# WiFiRadio_r1b4.net
KiCad netlist of a schematic drawn in EAGLE
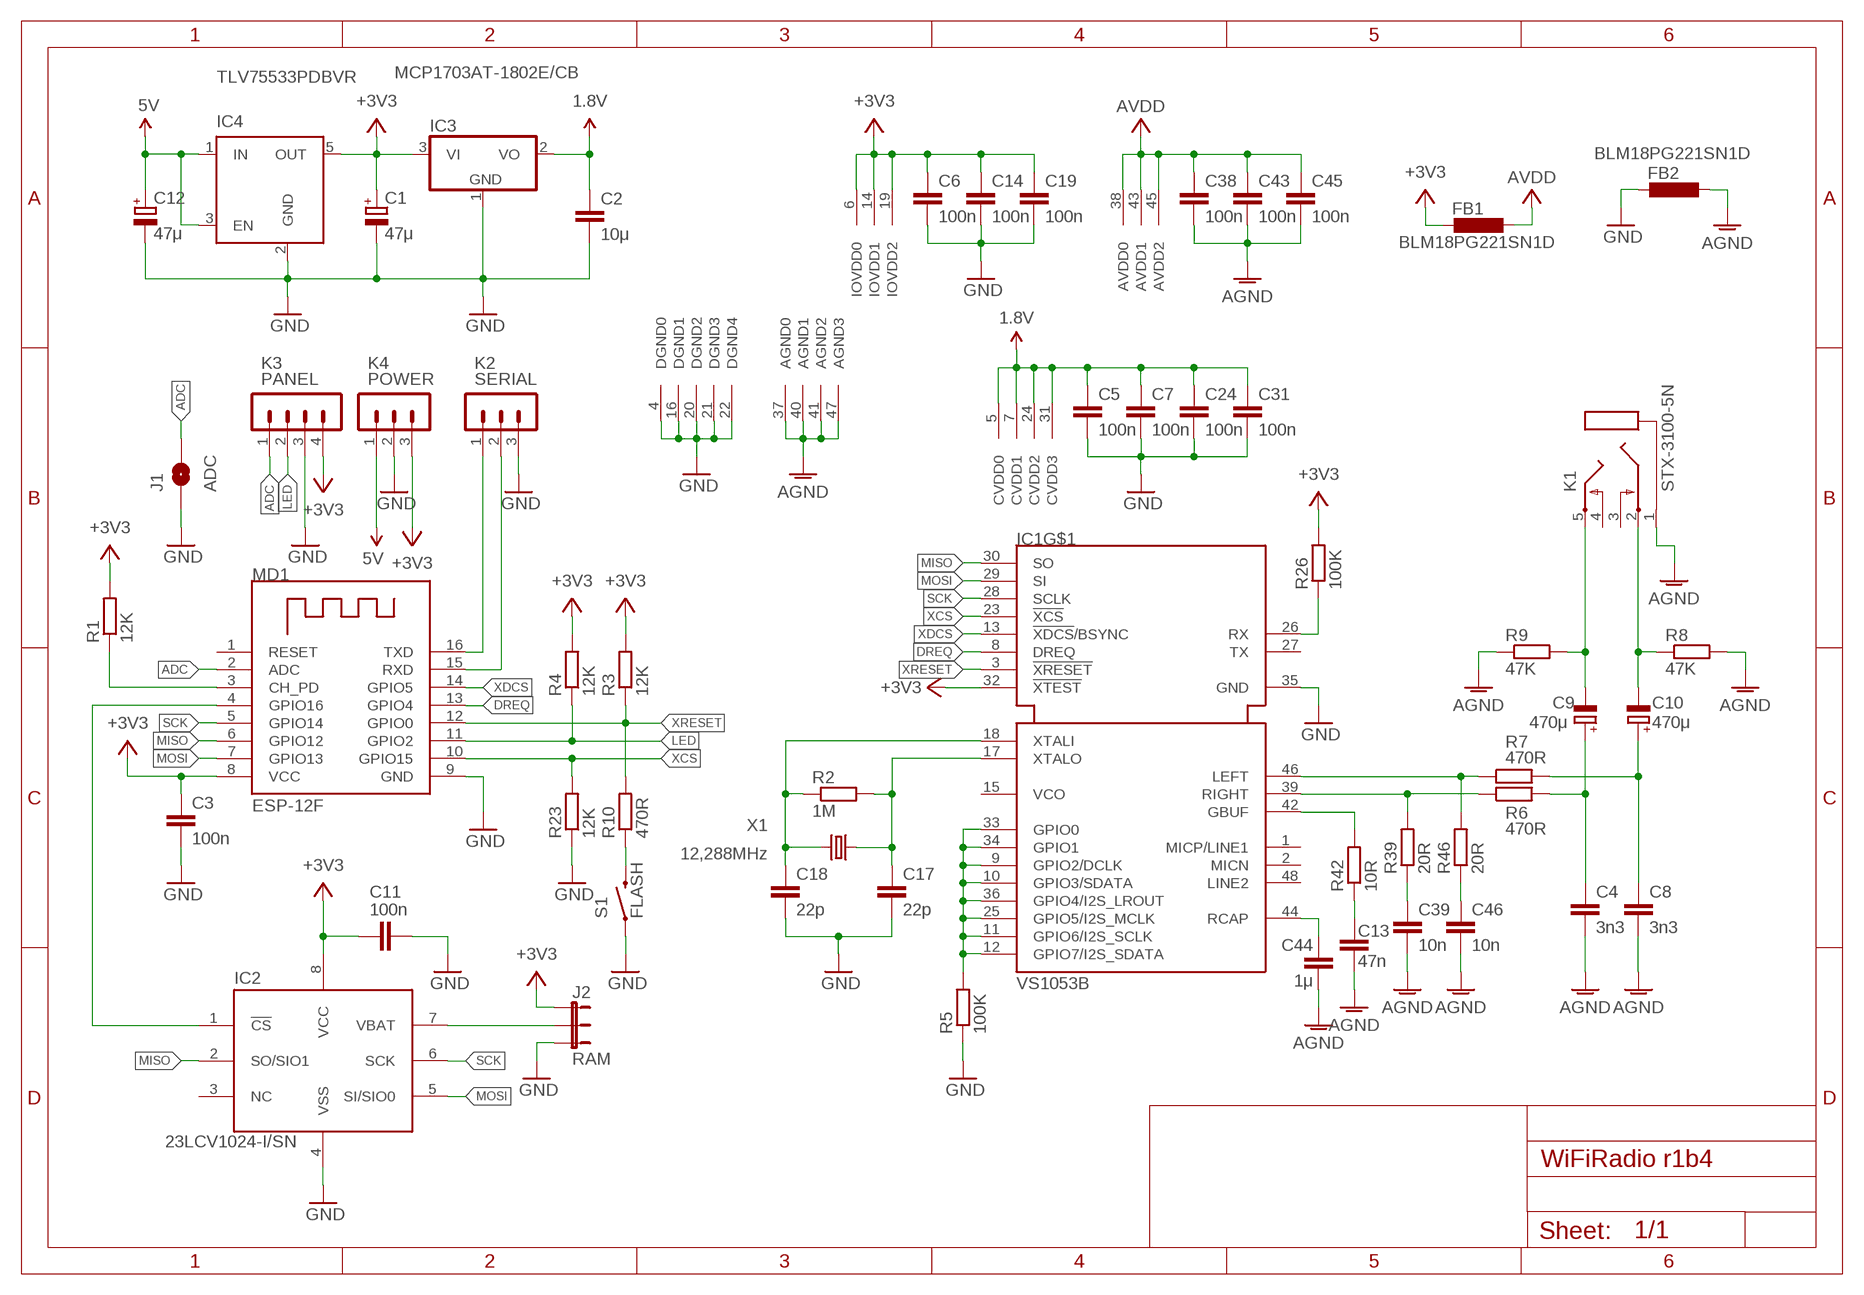
[diagram p0: schematic, sheet 1]

(export (version "E")
  (design (tool "Eeschema 10.0.6"))
  (components
    (comp (ref "C1")
      (value "47μ")
      (footprint "eagle-import:SMC_B")
      (libsource (lib "eagle-import") (part "rcl_334_CPOL-EUSMCB"))
    )
    (comp (ref "C2")
      (value "10μ")
      (footprint "eagle-import:C0805")
      (libsource (lib "eagle-import") (part "C-EUC0805"))
    )
    (comp (ref "C3")
      (value "100n")
      (footprint "eagle-import:C0603")
      (libsource (lib "eagle-import") (part "C-EUC0603"))
    )
    (comp (ref "C4")
      (value "3n3")
      (footprint "eagle-import:C0805")
      (libsource (lib "eagle-import") (part "C-EUC0805"))
    )
    (comp (ref "C5")
      (value "100n")
      (footprint "eagle-import:C0603")
      (libsource (lib "eagle-import") (part "C-EUC0603"))
    )
    (comp (ref "C6")
      (value "100n")
      (footprint "eagle-import:C0603")
      (libsource (lib "eagle-import") (part "C-EUC0603"))
    )
    (comp (ref "C7")
      (value "100n")
      (footprint "eagle-import:C0603")
      (libsource (lib "eagle-import") (part "C-EUC0603"))
    )
    (comp (ref "C8")
      (value "3n3")
      (footprint "eagle-import:C0805")
      (libsource (lib "eagle-import") (part "C-EUC0805"))
    )
    (comp (ref "C9")
      (value "470μ")
      (footprint "eagle-import:E3,5-8")
      (libsource (lib "eagle-import") (part "CPOL-EUE3.5-8"))
    )
    (comp (ref "C10")
      (value "470μ")
      (footprint "eagle-import:E3,5-8")
      (libsource (lib "eagle-import") (part "CPOL-EUE3.5-8"))
    )
    (comp (ref "C11")
      (value "100n")
      (footprint "eagle-import:C0603")
      (libsource (lib "eagle-import") (part "C-EUC0603"))
    )
    (comp (ref "C12")
      (value "47μ")
      (footprint "eagle-import:SMC_B")
      (libsource (lib "eagle-import") (part "rcl_334_CPOL-EUSMCB"))
    )
    (comp (ref "C13")
      (value "47n")
      (footprint "eagle-import:C0805")
      (libsource (lib "eagle-import") (part "C-EUC0805"))
    )
    (comp (ref "C14")
      (value "100n")
      (footprint "eagle-import:C0603")
      (libsource (lib "eagle-import") (part "C-EUC0603"))
    )
    (comp (ref "C17")
      (value "22p")
      (footprint "eagle-import:C0805")
      (libsource (lib "eagle-import") (part "C-EUC0805"))
    )
    (comp (ref "C18")
      (value "22p")
      (footprint "eagle-import:C0805")
      (libsource (lib "eagle-import") (part "C-EUC0805"))
    )
    (comp (ref "C19")
      (value "100n")
      (footprint "eagle-import:C0603")
      (libsource (lib "eagle-import") (part "C-EUC0603"))
    )
    (comp (ref "C24")
      (value "100n")
      (footprint "eagle-import:C0603")
      (libsource (lib "eagle-import") (part "C-EUC0603"))
    )
    (comp (ref "C31")
      (value "100n")
      (footprint "eagle-import:C0603")
      (libsource (lib "eagle-import") (part "C-EUC0603"))
    )
    (comp (ref "C38")
      (value "100n")
      (footprint "eagle-import:C0603")
      (libsource (lib "eagle-import") (part "C-EUC0603"))
    )
    (comp (ref "C39")
      (value "10n")
      (footprint "eagle-import:C0805")
      (libsource (lib "eagle-import") (part "C-EUC0805"))
    )
    (comp (ref "C43")
      (value "100n")
      (footprint "eagle-import:C0603")
      (libsource (lib "eagle-import") (part "C-EUC0603"))
    )
    (comp (ref "C44")
      (value "1μ")
      (footprint "eagle-import:C0805")
      (libsource (lib "eagle-import") (part "C-EUC0805"))
    )
    (comp (ref "C45")
      (value "100n")
      (footprint "eagle-import:C0603")
      (libsource (lib "eagle-import") (part "C-EUC0603"))
    )
    (comp (ref "C46")
      (value "10n")
      (footprint "eagle-import:C0805")
      (libsource (lib "eagle-import") (part "C-EUC0805"))
    )
    (comp (ref "FB1")
      (value "BLM18PG221SN1D")
      (footprint "eagle-import:L2012C")
      (libsource (lib "eagle-import") (part "L-EUL2012C"))
    )
    (comp (ref "FB2")
      (value "BLM18PG221SN1D")
      (footprint "eagle-import:L2012C")
      (libsource (lib "eagle-import") (part "L-EUL2012C"))
    )
    (comp (ref "IC1")
      (value "VS1053B")
      (footprint "eagle-import:LQFP48")
      (libsource (lib "eagle-import") (part "VS1053B"))
    )
    (comp (ref "IC2")
      (value "23LCV1024-I/SN")
      (footprint "eagle-import:SO-08")
      (libsource (lib "eagle-import") (part "23LCV1024-I/SN"))
    )
    (comp (ref "IC3")
      (value "MCP1703AT-1802E/CB")
      (footprint "eagle-import:SOT23")
      (libsource (lib "eagle-import") (part "MCP1703CB"))
    )
    (comp (ref "IC4")
      (value "TLV75533PDBVR")
      (footprint "eagle-import:SOT23-5")
      (libsource (lib "eagle-import") (part "TLV7555P-DBV"))
    )
    (comp (ref "J1")
      (value "ADC")
      (footprint "eagle-import:SJ_2S")
      (libsource (lib "eagle-import") (part "SOLDERJUMPER-OLDNC"))
    )
    (comp (ref "J2")
      (value "RAM")
      (footprint "eagle-import:SJ_3")
      (libsource (lib "eagle-import") (part "JUMPER-3SMD"))
    )
    (comp (ref "K1")
      (value "STX-3100-5N")
      (footprint "eagle-import:STX3100")
      (libsource (lib "eagle-import") (part "STEREOJACK"))
    )
    (comp (ref "K2")
      (value "SERIAL")
      (footprint "eagle-import:MA03-1")
      (libsource (lib "eagle-import") (part "MA03-1"))
    )
    (comp (ref "K3")
      (value "PANEL")
      (footprint "eagle-import:MA04-1")
      (libsource (lib "eagle-import") (part "MA04-1"))
    )
    (comp (ref "K4")
      (value "POWER")
      (footprint "eagle-import:MA03-1")
      (libsource (lib "eagle-import") (part "MA03-1"))
    )
    (comp (ref "MD1")
      (value "ESP-12F")
      (footprint "eagle-import:ESP-12F")
      (libsource (lib "eagle-import") (part "ESP-12F"))
    )
    (comp (ref "R1")
      (value "12K")
      (footprint "eagle-import:R0805")
      (libsource (lib "eagle-import") (part "R-EU_R0805"))
    )
    (comp (ref "R2")
      (value "1M")
      (footprint "eagle-import:R0805")
      (libsource (lib "eagle-import") (part "R-EU_R0805"))
    )
    (comp (ref "R3")
      (value "12K")
      (footprint "eagle-import:R0805")
      (libsource (lib "eagle-import") (part "R-EU_R0805"))
    )
    (comp (ref "R4")
      (value "12K")
      (footprint "eagle-import:R0805")
      (libsource (lib "eagle-import") (part "R-EU_R0805"))
    )
    (comp (ref "R5")
      (value "100K")
      (footprint "eagle-import:R0805")
      (libsource (lib "eagle-import") (part "R-EU_R0805"))
    )
    (comp (ref "R6")
      (value "470R")
      (footprint "eagle-import:R0805")
      (libsource (lib "eagle-import") (part "R-EU_R0805"))
    )
    (comp (ref "R7")
      (value "470R")
      (footprint "eagle-import:R0805")
      (libsource (lib "eagle-import") (part "R-EU_R0805"))
    )
    (comp (ref "R8")
      (value "47K")
      (footprint "eagle-import:R0805")
      (libsource (lib "eagle-import") (part "R-EU_R0805"))
    )
    (comp (ref "R9")
      (value "47K")
      (footprint "eagle-import:R0805")
      (libsource (lib "eagle-import") (part "R-EU_R0805"))
    )
    (comp (ref "R10")
      (value "470R")
      (footprint "eagle-import:R0805")
      (libsource (lib "eagle-import") (part "R-EU_R0805"))
    )
    (comp (ref "R23")
      (value "12K")
      (footprint "eagle-import:R0805")
      (libsource (lib "eagle-import") (part "R-EU_R0805"))
    )
    (comp (ref "R26")
      (value "100K")
      (footprint "eagle-import:R0805")
      (libsource (lib "eagle-import") (part "R-EU_R0805"))
    )
    (comp (ref "R39")
      (value "20R")
      (footprint "eagle-import:R0805")
      (libsource (lib "eagle-import") (part "R-EU_R0805"))
    )
    (comp (ref "R42")
      (value "10R")
      (footprint "eagle-import:R0805")
      (libsource (lib "eagle-import") (part "R-EU_R0805"))
    )
    (comp (ref "R46")
      (value "20R")
      (footprint "eagle-import:R0805")
      (libsource (lib "eagle-import") (part "R-EU_R0805"))
    )
    (comp (ref "S1")
      (value "FLASH")
      (footprint "eagle-import:TACTILE-SWITCH-SMD")
      (libsource (lib "eagle-import") (part "SWITCH-MOMENTARY-2SMD"))
    )
    (comp (ref "X1")
      (value "12,288MHz")
      (footprint "eagle-import:HC49_S")
      (libsource (lib "eagle-import") (part "CRYSTALHC49S"))
    )
  )
  (nets
    (net (code "1") (name "+3V3") (class "Default")
      (node (ref "C1") (pin "+") (pinfunction "+_+") (pintype "passive"))
      (node (ref "C11") (pin "1") (pinfunction "1_1") (pintype "passive"))
      (node (ref "C14") (pin "1") (pinfunction "1_1") (pintype "passive"))
      (node (ref "C19") (pin "1") (pinfunction "1_1") (pintype "passive"))
      (node (ref "C3") (pin "1") (pinfunction "1_1") (pintype "passive"))
      (node (ref "C6") (pin "1") (pinfunction "1_1") (pintype "passive"))
      (node (ref "FB1") (pin "2") (pinfunction "2_2") (pintype "passive"))
      (node (ref "IC1") (pin "14") (pinfunction "IOVDD1_14") (pintype "power_in"))
      (node (ref "IC1") (pin "19") (pinfunction "IOVDD2_19") (pintype "power_in"))
      (node (ref "IC1") (pin "32") (pinfunction "~{XTEST}_32") (pintype "input"))
      (node (ref "IC1") (pin "6") (pinfunction "IOVDD0_6") (pintype "power_in"))
      (node (ref "IC2") (pin "8") (pinfunction "VCC_8") (pintype "power_in"))
      (node (ref "IC3") (pin "3") (pinfunction "VI_3") (pintype "input"))
      (node (ref "IC4") (pin "5") (pinfunction "OUT_5") (pintype "output"))
      (node (ref "J2") (pin "1") (pinfunction "1_1") (pintype "passive"))
      (node (ref "K3") (pin "4") (pinfunction "4_4") (pintype "passive"))
      (node (ref "K4") (pin "3") (pinfunction "3_3") (pintype "passive"))
      (node (ref "MD1") (pin "8") (pinfunction "VCC_8") (pintype "power_in"))
      (node (ref "R1") (pin "2") (pinfunction "2_2") (pintype "passive"))
      (node (ref "R26") (pin "2") (pinfunction "2_2") (pintype "passive"))
      (node (ref "R3") (pin "2") (pinfunction "2_2") (pintype "passive"))
      (node (ref "R4") (pin "2") (pinfunction "2_2") (pintype "passive"))
    )
    (net (code "2") (name "1.8V") (class "Default")
      (node (ref "C2") (pin "1") (pinfunction "1_1") (pintype "passive"))
      (node (ref "C24") (pin "1") (pinfunction "1_1") (pintype "passive"))
      (node (ref "C31") (pin "1") (pinfunction "1_1") (pintype "passive"))
      (node (ref "C5") (pin "1") (pinfunction "1_1") (pintype "passive"))
      (node (ref "C7") (pin "1") (pinfunction "1_1") (pintype "passive"))
      (node (ref "IC1") (pin "24") (pinfunction "CVDD2_24") (pintype "power_in"))
      (node (ref "IC1") (pin "31") (pinfunction "CVDD3_31") (pintype "power_in"))
      (node (ref "IC1") (pin "5") (pinfunction "CVDD0_5") (pintype "power_in"))
      (node (ref "IC1") (pin "7") (pinfunction "CVDD1_7") (pintype "power_in"))
      (node (ref "IC3") (pin "2") (pinfunction "VO_2") (pintype "passive"))
    )
    (net (code "3") (name "5V") (class "Default")
      (node (ref "C12") (pin "+") (pinfunction "+_+") (pintype "passive"))
      (node (ref "IC4") (pin "1") (pinfunction "IN_1") (pintype "input"))
      (node (ref "IC4") (pin "3") (pinfunction "EN_3") (pintype "input"))
      (node (ref "K4") (pin "1") (pinfunction "1_1") (pintype "passive"))
    )
    (net (code "4") (name "ADC") (class "Default")
      (node (ref "J1") (pin "2") (pinfunction "2_2") (pintype "passive"))
      (node (ref "K3") (pin "1") (pinfunction "1_1") (pintype "passive"))
      (node (ref "MD1") (pin "2") (pinfunction "ADC_2") (pintype "passive"))
    )
    (net (code "5") (name "AGND") (class "Default")
      (node (ref "C13") (pin "2") (pinfunction "2_2") (pintype "passive"))
      (node (ref "C38") (pin "2") (pinfunction "2_2") (pintype "passive"))
      (node (ref "C39") (pin "2") (pinfunction "2_2") (pintype "passive"))
      (node (ref "C4") (pin "2") (pinfunction "2_2") (pintype "passive"))
      (node (ref "C43") (pin "2") (pinfunction "2_2") (pintype "passive"))
      (node (ref "C44") (pin "2") (pinfunction "2_2") (pintype "passive"))
      (node (ref "C45") (pin "2") (pinfunction "2_2") (pintype "passive"))
      (node (ref "C46") (pin "2") (pinfunction "2_2") (pintype "passive"))
      (node (ref "C8") (pin "2") (pinfunction "2_2") (pintype "passive"))
      (node (ref "FB2") (pin "1") (pinfunction "1_1") (pintype "passive"))
      (node (ref "IC1") (pin "37") (pinfunction "AGND0_37") (pintype "power_in"))
      (node (ref "IC1") (pin "40") (pinfunction "AGND1_40") (pintype "power_in"))
      (node (ref "IC1") (pin "41") (pinfunction "AGND2_41") (pintype "power_in"))
      (node (ref "IC1") (pin "47") (pinfunction "AGND3_47") (pintype "power_in"))
      (node (ref "K1") (pin "1") (pinfunction "1_1") (pintype "passive"))
      (node (ref "R8") (pin "2") (pinfunction "2_2") (pintype "passive"))
      (node (ref "R9") (pin "1") (pinfunction "1_1") (pintype "passive"))
    )
    (net (code "6") (name "AVDD") (class "Default")
      (node (ref "C38") (pin "1") (pinfunction "1_1") (pintype "passive"))
      (node (ref "C43") (pin "1") (pinfunction "1_1") (pintype "passive"))
      (node (ref "C45") (pin "1") (pinfunction "1_1") (pintype "passive"))
      (node (ref "FB1") (pin "1") (pinfunction "1_1") (pintype "passive"))
      (node (ref "IC1") (pin "38") (pinfunction "AVDD0_38") (pintype "power_in"))
      (node (ref "IC1") (pin "43") (pinfunction "AVDD1_43") (pintype "power_in"))
      (node (ref "IC1") (pin "45") (pinfunction "AVDD2_45") (pintype "power_in"))
    )
    (net (code "7") (name "DREQ") (class "Default")
      (node (ref "IC1") (pin "8") (pinfunction "DREQ_8") (pintype "output"))
      (node (ref "MD1") (pin "13") (pinfunction "GPIO4_13") (pintype "bidirectional"))
    )
    (net (code "8") (name "GND") (class "Default")
      (node (ref "C1") (pin "-") (pinfunction "-_-") (pintype "passive"))
      (node (ref "C11") (pin "2") (pinfunction "2_2") (pintype "passive"))
      (node (ref "C12") (pin "-") (pinfunction "-_-") (pintype "passive"))
      (node (ref "C14") (pin "2") (pinfunction "2_2") (pintype "passive"))
      (node (ref "C17") (pin "2") (pinfunction "2_2") (pintype "passive"))
      (node (ref "C18") (pin "2") (pinfunction "2_2") (pintype "passive"))
      (node (ref "C19") (pin "2") (pinfunction "2_2") (pintype "passive"))
      (node (ref "C2") (pin "2") (pinfunction "2_2") (pintype "passive"))
      (node (ref "C24") (pin "2") (pinfunction "2_2") (pintype "passive"))
      (node (ref "C3") (pin "2") (pinfunction "2_2") (pintype "passive"))
      (node (ref "C31") (pin "2") (pinfunction "2_2") (pintype "passive"))
      (node (ref "C5") (pin "2") (pinfunction "2_2") (pintype "passive"))
      (node (ref "C6") (pin "2") (pinfunction "2_2") (pintype "passive"))
      (node (ref "C7") (pin "2") (pinfunction "2_2") (pintype "passive"))
      (node (ref "FB2") (pin "2") (pinfunction "2_2") (pintype "passive"))
      (node (ref "IC1") (pin "16") (pinfunction "DGND1_16") (pintype "power_in"))
      (node (ref "IC1") (pin "20") (pinfunction "DGND2_20") (pintype "power_in"))
      (node (ref "IC1") (pin "21") (pinfunction "DGND3_21") (pintype "power_in"))
      (node (ref "IC1") (pin "22") (pinfunction "DGND4_22") (pintype "power_in"))
      (node (ref "IC1") (pin "35") (pinfunction "GND_35") (pintype "power_in"))
      (node (ref "IC1") (pin "4") (pinfunction "DGND0_4") (pintype "power_in"))
      (node (ref "IC2") (pin "4") (pinfunction "VSS_4") (pintype "power_in"))
      (node (ref "IC3") (pin "1") (pinfunction "GND_1") (pintype "passive"))
      (node (ref "IC4") (pin "2") (pinfunction "GND_2") (pintype "power_in"))
      (node (ref "J1") (pin "1") (pinfunction "1_1") (pintype "passive"))
      (node (ref "J2") (pin "3") (pinfunction "3_3") (pintype "passive"))
      (node (ref "K2") (pin "3") (pinfunction "3_3") (pintype "passive"))
      (node (ref "K3") (pin "3") (pinfunction "3_3") (pintype "passive"))
      (node (ref "K4") (pin "2") (pinfunction "2_2") (pintype "passive"))
      (node (ref "MD1") (pin "9") (pinfunction "GND_9") (pintype "power_in"))
      (node (ref "R23") (pin "1") (pinfunction "1_1") (pintype "passive"))
      (node (ref "R5") (pin "1") (pinfunction "1_1") (pintype "passive"))
      (node (ref "S1") (pin "1") (pinfunction "1_1") (pintype "passive"))
    )
    (net (code "9") (name "LED") (class "Default")
      (node (ref "K3") (pin "2") (pinfunction "2_2") (pintype "passive"))
      (node (ref "MD1") (pin "11") (pinfunction "GPIO2_11") (pintype "bidirectional"))
      (node (ref "R4") (pin "1") (pinfunction "1_1") (pintype "passive"))
    )
    (net (code "10") (name "MISO") (class "Default")
      (node (ref "IC1") (pin "30") (pinfunction "SO_30") (pintype "output"))
      (node (ref "IC2") (pin "2") (pinfunction "SO/SIO1_2") (pintype "bidirectional"))
      (node (ref "MD1") (pin "6") (pinfunction "GPIO12_6") (pintype "bidirectional"))
    )
    (net (code "11") (name "MOSI") (class "Default")
      (node (ref "IC1") (pin "29") (pinfunction "SI_29") (pintype "input"))
      (node (ref "IC2") (pin "5") (pinfunction "SI/SIO0_5") (pintype "bidirectional"))
      (node (ref "MD1") (pin "7") (pinfunction "GPIO13_7") (pintype "bidirectional"))
    )
    (net (code "12") (name "Net-(C4-Pad1)") (class "Default")
      (node (ref "C4") (pin "1") (pinfunction "1_1") (pintype "passive"))
      (node (ref "C9") (pin "+") (pinfunction "+_+") (pintype "passive"))
      (node (ref "R6") (pin "2") (pinfunction "2_2") (pintype "passive"))
    )
    (net (code "13") (name "Net-(C9-Pad-)") (class "Default")
      (node (ref "C9") (pin "-") (pinfunction "-_-") (pintype "passive"))
      (node (ref "K1") (pin "5") (pinfunction "5_5") (pintype "passive"))
      (node (ref "R9") (pin "2") (pinfunction "2_2") (pintype "passive"))
    )
    (net (code "14") (name "Net-(C10-Pad+)") (class "Default")
      (node (ref "C10") (pin "+") (pinfunction "+_+") (pintype "passive"))
      (node (ref "C8") (pin "1") (pinfunction "1_1") (pintype "passive"))
      (node (ref "R7") (pin "2") (pinfunction "2_2") (pintype "passive"))
    )
    (net (code "15") (name "Net-(C10-Pad-)") (class "Default")
      (node (ref "C10") (pin "-") (pinfunction "-_-") (pintype "passive"))
      (node (ref "K1") (pin "2") (pinfunction "2_2") (pintype "passive"))
      (node (ref "R8") (pin "1") (pinfunction "1_1") (pintype "passive"))
    )
    (net (code "16") (name "Net-(C13-Pad1)") (class "Default")
      (node (ref "C13") (pin "1") (pinfunction "1_1") (pintype "passive"))
      (node (ref "R42") (pin "1") (pinfunction "1_1") (pintype "passive"))
    )
    (net (code "17") (name "Net-(C39-Pad1)") (class "Default")
      (node (ref "C39") (pin "1") (pinfunction "1_1") (pintype "passive"))
      (node (ref "R39") (pin "1") (pinfunction "1_1") (pintype "passive"))
    )
    (net (code "18") (name "Net-(C46-Pad1)") (class "Default")
      (node (ref "C46") (pin "1") (pinfunction "1_1") (pintype "passive"))
      (node (ref "R46") (pin "1") (pinfunction "1_1") (pintype "passive"))
    )
    (net (code "19") (name "Net-(IC1A-GBUF)") (class "Default")
      (node (ref "IC1") (pin "42") (pinfunction "GBUF_42") (pintype "output"))
      (node (ref "R42") (pin "2") (pinfunction "2_2") (pintype "passive"))
    )
    (net (code "20") (name "Net-(IC1A-GPIO0)") (class "Default")
      (node (ref "IC1") (pin "10") (pinfunction "GPIO3/SDATA_10") (pintype "bidirectional"))
      (node (ref "IC1") (pin "11") (pinfunction "GPIO6/I2S_SCLK_11") (pintype "bidirectional"))
      (node (ref "IC1") (pin "12") (pinfunction "GPIO7/I2S_SDATA_12") (pintype "bidirectional"))
      (node (ref "IC1") (pin "25") (pinfunction "GPIO5/I2S_MCLK_25") (pintype "bidirectional"))
      (node (ref "IC1") (pin "33") (pinfunction "GPIO0_33") (pintype "bidirectional"))
      (node (ref "IC1") (pin "34") (pinfunction "GPIO1_34") (pintype "bidirectional"))
      (node (ref "IC1") (pin "36") (pinfunction "GPIO4/I2S_LROUT_36") (pintype "bidirectional"))
      (node (ref "IC1") (pin "9") (pinfunction "GPIO2/DCLK_9") (pintype "bidirectional"))
      (node (ref "R5") (pin "2") (pinfunction "2_2") (pintype "passive"))
    )
    (net (code "21") (name "Net-(IC1A-LEFT)") (class "Default")
      (node (ref "IC1") (pin "46") (pinfunction "LEFT_46") (pintype "output"))
      (node (ref "R46") (pin "2") (pinfunction "2_2") (pintype "passive"))
      (node (ref "R7") (pin "1") (pinfunction "1_1") (pintype "passive"))
    )
    (net (code "22") (name "Net-(IC1A-RCAP)") (class "Default")
      (node (ref "C44") (pin "1") (pinfunction "1_1") (pintype "passive"))
      (node (ref "IC1") (pin "44") (pinfunction "RCAP_44") (pintype "bidirectional"))
    )
    (net (code "23") (name "Net-(IC1A-RIGHT)") (class "Default")
      (node (ref "IC1") (pin "39") (pinfunction "RIGHT_39") (pintype "output"))
      (node (ref "R39") (pin "2") (pinfunction "2_2") (pintype "passive"))
      (node (ref "R6") (pin "1") (pinfunction "1_1") (pintype "passive"))
    )
    (net (code "24") (name "Net-(IC1A-RX)") (class "Default")
      (node (ref "IC1") (pin "26") (pinfunction "RX_26") (pintype "input"))
      (node (ref "R26") (pin "1") (pinfunction "1_1") (pintype "passive"))
    )
    (net (code "25") (name "Net-(IC1A-XTALI)") (class "Default")
      (node (ref "C18") (pin "1") (pinfunction "1_1") (pintype "passive"))
      (node (ref "IC1") (pin "18") (pinfunction "XTALI_18") (pintype "input"))
      (node (ref "R2") (pin "1") (pinfunction "1_1") (pintype "passive"))
      (node (ref "X1") (pin "2") (pinfunction "2_2") (pintype "passive"))
    )
    (net (code "26") (name "Net-(IC1A-XTALO)") (class "Default")
      (node (ref "C17") (pin "1") (pinfunction "1_1") (pintype "passive"))
      (node (ref "IC1") (pin "17") (pinfunction "XTALO_17") (pintype "output"))
      (node (ref "R2") (pin "2") (pinfunction "2_2") (pintype "passive"))
      (node (ref "X1") (pin "1") (pinfunction "1_1") (pintype "passive"))
    )
    (net (code "27") (name "Net-(IC2-VBAT)") (class "Default")
      (node (ref "IC2") (pin "7") (pinfunction "VBAT_7") (pintype "power_in"))
      (node (ref "J2") (pin "2") (pinfunction "2_2") (pintype "passive"))
    )
    (net (code "28") (name "Net-(IC2-~{CS})") (class "Default")
      (node (ref "IC2") (pin "1") (pinfunction "~{CS}_1") (pintype "input"))
      (node (ref "MD1") (pin "4") (pinfunction "GPIO16_4") (pintype "bidirectional"))
    )
    (net (code "29") (name "Net-(MD1-CH_PD)") (class "Default")
      (node (ref "MD1") (pin "3") (pinfunction "CH_PD_3") (pintype "input"))
      (node (ref "R1") (pin "1") (pinfunction "1_1") (pintype "passive"))
    )
    (net (code "30") (name "Net-(MD1-RXD)") (class "Default")
      (node (ref "K2") (pin "2") (pinfunction "2_2") (pintype "passive"))
      (node (ref "MD1") (pin "15") (pinfunction "RXD_15") (pintype "input"))
    )
    (net (code "31") (name "Net-(MD1-TXD)") (class "Default")
      (node (ref "K2") (pin "1") (pinfunction "1_1") (pintype "passive"))
      (node (ref "MD1") (pin "16") (pinfunction "TXD_16") (pintype "output"))
    )
    (net (code "32") (name "Net-(S1-2)") (class "Default")
      (node (ref "R10") (pin "1") (pinfunction "1_1") (pintype "passive"))
      (node (ref "S1") (pin "3") (pinfunction "2_3") (pintype "passive"))
    )
    (net (code "33") (name "SCK") (class "Default")
      (node (ref "IC1") (pin "28") (pinfunction "SCLK_28") (pintype "input"))
      (node (ref "IC2") (pin "6") (pinfunction "SCK_6") (pintype "input"))
      (node (ref "MD1") (pin "5") (pinfunction "GPIO14_5") (pintype "bidirectional"))
    )
    (net (code "34") (name "XCS") (class "Default")
      (node (ref "IC1") (pin "23") (pinfunction "~{XCS}_23") (pintype "input"))
      (node (ref "MD1") (pin "10") (pinfunction "GPIO15_10") (pintype "bidirectional"))
      (node (ref "R23") (pin "2") (pinfunction "2_2") (pintype "passive"))
    )
    (net (code "35") (name "XDCS") (class "Default")
      (node (ref "IC1") (pin "13") (pinfunction "~{XDCS}/BSYNC_13") (pintype "input"))
      (node (ref "MD1") (pin "14") (pinfunction "GPIO5_14") (pintype "bidirectional"))
    )
    (net (code "36") (name "XRESET") (class "Default")
      (node (ref "IC1") (pin "3") (pinfunction "~{XRESET}_3") (pintype "input"))
      (node (ref "MD1") (pin "12") (pinfunction "GPIO0_12") (pintype "bidirectional"))
      (node (ref "R10") (pin "2") (pinfunction "2_2") (pintype "passive"))
      (node (ref "R3") (pin "1") (pinfunction "1_1") (pintype "passive"))
    )
    (net (code "37") (name "unconnected-(IC1A-LINE2-Pad48)") (class "Default")
      (node (ref "IC1") (pin "48") (pinfunction "LINE2_48") (pintype "input"))
    )
    (net (code "38") (name "unconnected-(IC1A-MICN-Pad2)") (class "Default")
      (node (ref "IC1") (pin "2") (pinfunction "MICN_2") (pintype "input"))
    )
    (net (code "39") (name "unconnected-(IC1A-MICP{slash}LINE1-Pad1)") (class "Default")
      (node (ref "IC1") (pin "1") (pinfunction "MICP/LINE1_1") (pintype "input"))
    )
    (net (code "40") (name "unconnected-(IC1A-TX-Pad27)") (class "Default")
      (node (ref "IC1") (pin "27") (pinfunction "TX_27") (pintype "output"))
    )
    (net (code "41") (name "unconnected-(IC1A-VCO-Pad15)") (class "Default")
      (node (ref "IC1") (pin "15") (pinfunction "VCO_15") (pintype "output"))
    )
    (net (code "42") (name "unconnected-(IC2-NC-Pad3)") (class "Default")
      (node (ref "IC2") (pin "3") (pinfunction "NC_3") (pintype "no_connect"))
    )
    (net (code "43") (name "unconnected-(K1-Pad3)") (class "Default")
      (node (ref "K1") (pin "3") (pinfunction "3_3") (pintype "passive"))
    )
    (net (code "44") (name "unconnected-(K1-Pad4)") (class "Default")
      (node (ref "K1") (pin "4") (pinfunction "4_4") (pintype "passive"))
    )
    (net (code "45") (name "unconnected-(MD1-RESET-Pad1)") (class "Default")
      (node (ref "MD1") (pin "1") (pinfunction "RESET_1") (pintype "input"))
    )
  )
)
